# radio.net
KiCad netlist of a schematic drawn in EAGLE
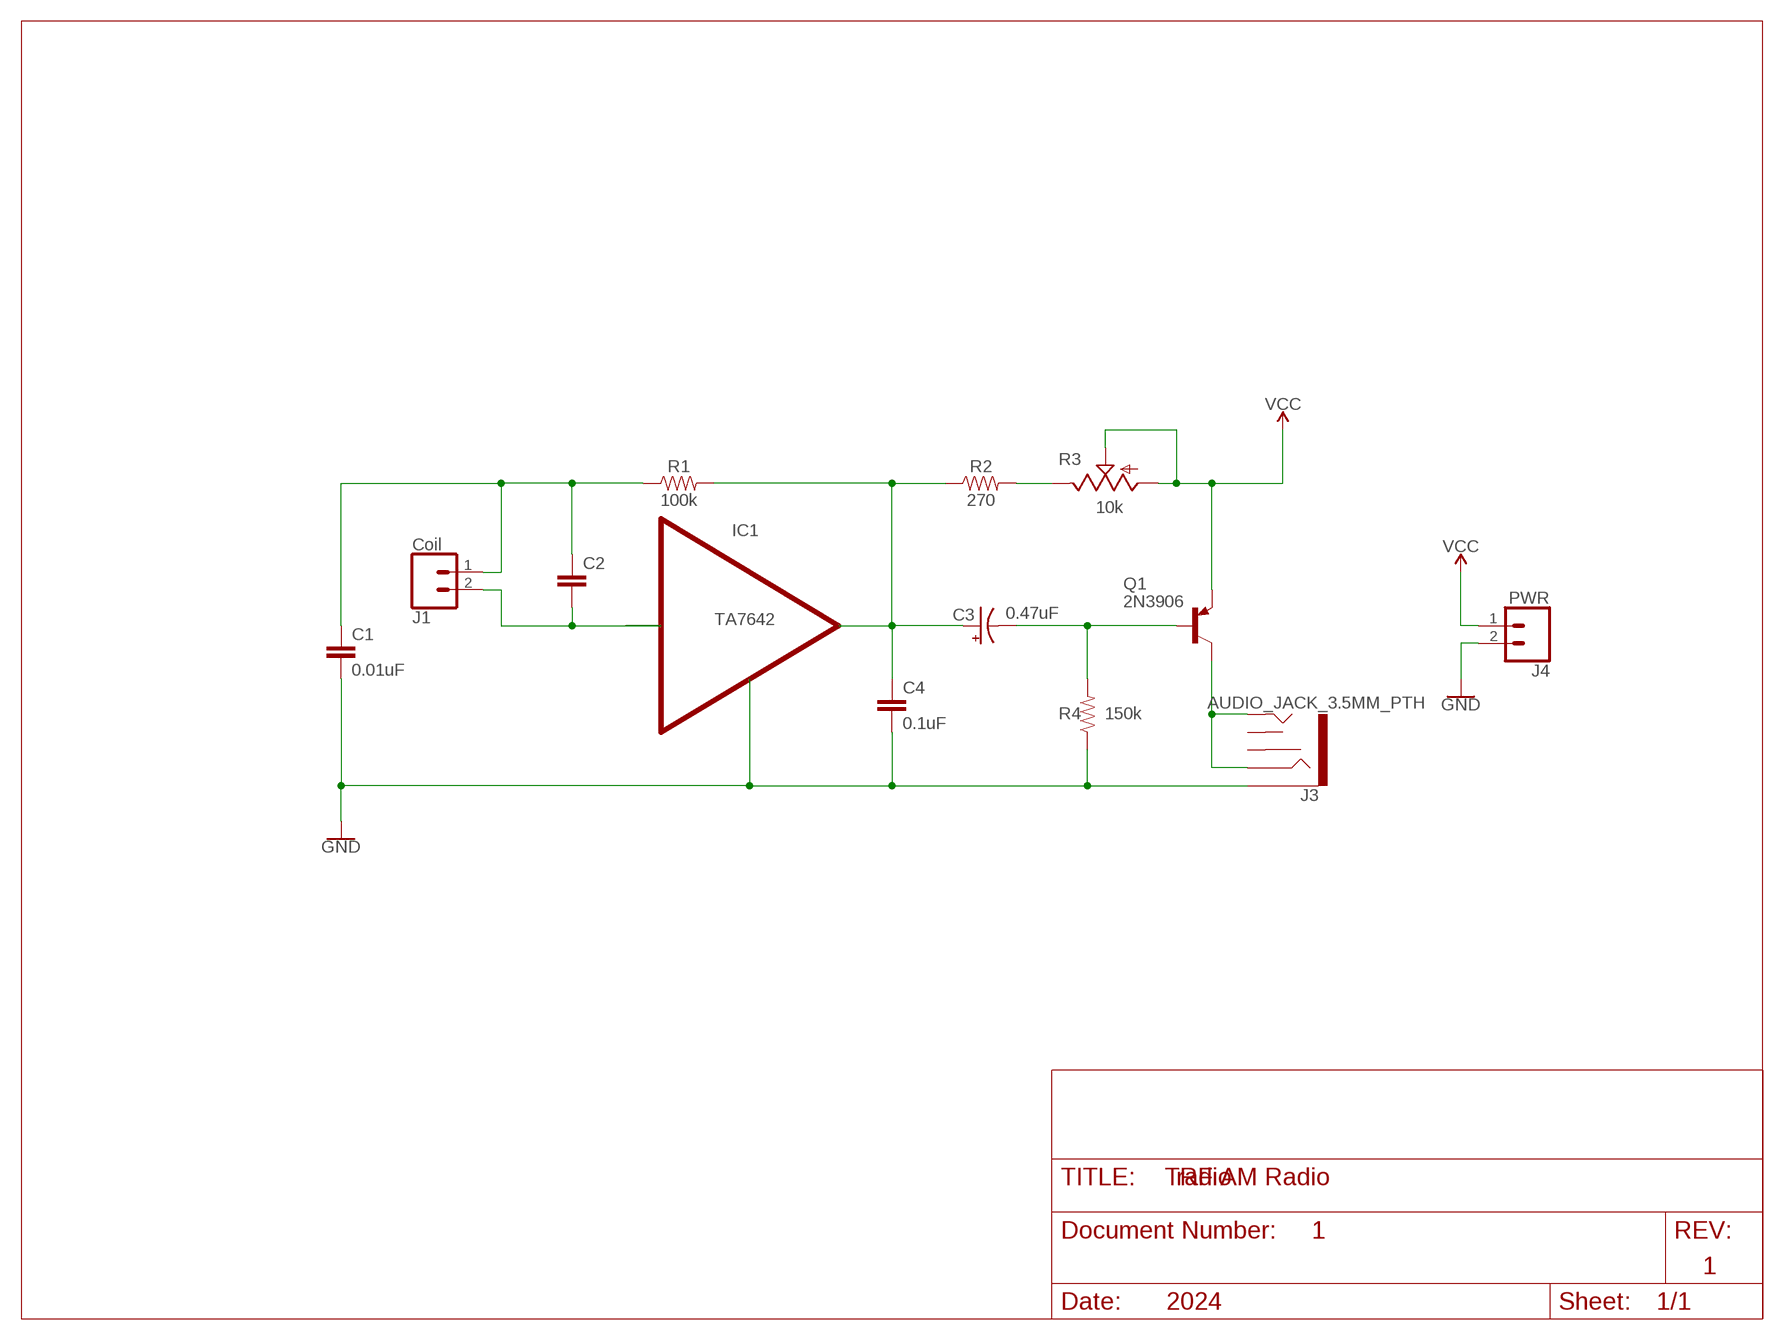
[diagram p0: schematic, sheet 1]

(export (version "E")
  (design (tool "Eeschema 10.0.6"))
  (components
    (comp (ref "C1")
      (value "0.01uF")
      (footprint "eagle-import:CAP-PTH-2.54")
      (libsource (lib "eagle-import") (part "22PF-PTH-2.54MM-200V-5%"))
    )
    (comp (ref "C2")
      (value "22PF-PTH-2.54MM-200V-5%")
      (footprint "eagle-import:CAP-PTH-2.54")
      (libsource (lib "eagle-import") (part "22PF-PTH-2.54MM-200V-5%"))
    )
    (comp (ref "C3")
      (value "0.47uF")
      (footprint "eagle-import:CPOL-RADIAL-2.5MM-5MM")
      (libsource (lib "eagle-import") (part "10UF-POLAR-RADIAL-2.5MM-25V-20%"))
    )
    (comp (ref "C4")
      (value "0.1uF")
      (footprint "eagle-import:CAP-PTH-2.54")
      (libsource (lib "eagle-import") (part "22PF-PTH-2.54MM-200V-5%"))
    )
    (comp (ref "IC1")
      (value "TA7642")
      (footprint "eagle-import:TO92")
      (libsource (lib "eagle-import") (part "TA7642"))
    )
    (comp (ref "J1")
      (value "Coil")
      (footprint "eagle-import:1X02")
      (libsource (lib "eagle-import") (part "CONN_02"))
    )
    (comp (ref "J3")
      (value "AUDIO_JACK_3.5MM_PTH")
      (footprint "eagle-import:AUDIO-JACK")
      (libsource (lib "eagle-import") (part "AUDIO_JACK_3.5MM_PTH"))
    )
    (comp (ref "J4")
      (value "PWR")
      (footprint "eagle-import:1X02")
      (libsource (lib "eagle-import") (part "CONN_02"))
    )
    (comp (ref "Q1")
      (value "2N3906")
      (footprint "eagle-import:TO92")
      (libsource (lib "eagle-import") (part "2N3906"))
    )
    (comp (ref "R1")
      (value "100k")
      (footprint "eagle-import:AXIAL-0.3")
      (libsource (lib "eagle-import") (part "RESISTORAXIAL-0.3"))
    )
    (comp (ref "R2")
      (value "270")
      (footprint "eagle-import:AXIAL-0.3")
      (libsource (lib "eagle-import") (part "RESISTORAXIAL-0.3"))
    )
    (comp (ref "R3")
      (value "10k")
      (footprint "eagle-import:B25P")
      (libsource (lib "eagle-import") (part "TRIM_US-B25P"))
    )
    (comp (ref "R4")
      (value "150k")
      (footprint "eagle-import:AXIAL-0.3")
      (libsource (lib "eagle-import") (part "RESISTORAXIAL-0.3"))
    )
  )
  (nets
    (net (code "1") (name "GND") (class "Default")
      (node (ref "C1") (pin "2") (pinfunction "2_2") (pintype "passive"))
      (node (ref "C4") (pin "2") (pinfunction "2_2") (pintype "passive"))
      (node (ref "IC1") (pin "2") (pinfunction "GND_2") (pintype "passive"))
      (node (ref "J3") (pin "SLEEVE") (pinfunction "SLEEVE_SLEEVE") (pintype "bidirectional"))
      (node (ref "J4") (pin "2") (pinfunction "2_2") (pintype "passive"))
      (node (ref "R4") (pin "P$1") (pinfunction "1_P$1") (pintype "passive"))
    )
    (net (code "2") (name "Net-(C3-+)") (class "Default")
      (node (ref "C3") (pin "1") (pinfunction "+_1") (pintype "passive"))
      (node (ref "C4") (pin "1") (pinfunction "1_1") (pintype "passive"))
      (node (ref "IC1") (pin "1") (pinfunction "OUT_1") (pintype "passive"))
      (node (ref "R1") (pin "P$2") (pinfunction "2_P$2") (pintype "passive"))
      (node (ref "R2") (pin "P$1") (pinfunction "1_P$1") (pintype "passive"))
    )
    (net (code "3") (name "Net-(C3--)") (class "Default")
      (node (ref "C3") (pin "2") (pinfunction "-_2") (pintype "passive"))
      (node (ref "Q1") (pin "2") (pinfunction "B_2") (pintype "passive"))
      (node (ref "R4") (pin "P$2") (pinfunction "2_P$2") (pintype "passive"))
    )
    (net (code "4") (name "Net-(IC1-INPUT)") (class "Default")
      (node (ref "C2") (pin "2") (pinfunction "2_2") (pintype "passive"))
      (node (ref "IC1") (pin "3") (pinfunction "INPUT_3") (pintype "passive"))
      (node (ref "J1") (pin "2") (pinfunction "2_2") (pintype "passive"))
    )
    (net (code "5") (name "Net-(Q1-C)") (class "Default")
      (node (ref "J3") (pin "RING") (pinfunction "RING_RING") (pintype "bidirectional"))
      (node (ref "J3") (pin "TIP") (pinfunction "TIP_TIP") (pintype "bidirectional"))
      (node (ref "Q1") (pin "1") (pinfunction "C_1") (pintype "passive"))
    )
    (net (code "6") (name "Net-(R1-1)") (class "Default")
      (node (ref "C1") (pin "1") (pinfunction "1_1") (pintype "passive"))
      (node (ref "C2") (pin "1") (pinfunction "1_1") (pintype "passive"))
      (node (ref "J1") (pin "1") (pinfunction "1_1") (pintype "passive"))
      (node (ref "R1") (pin "P$1") (pinfunction "1_P$1") (pintype "passive"))
    )
    (net (code "7") (name "Net-(R2-2)") (class "Default")
      (node (ref "R2") (pin "P$2") (pinfunction "2_P$2") (pintype "passive"))
      (node (ref "R3") (pin "E") (pinfunction "E_E") (pintype "passive"))
    )
    (net (code "8") (name "VCC") (class "Default")
      (node (ref "J4") (pin "1") (pinfunction "1_1") (pintype "passive"))
      (node (ref "Q1") (pin "3") (pinfunction "E_3") (pintype "passive"))
      (node (ref "R3") (pin "A") (pinfunction "A_A") (pintype "passive"))
      (node (ref "R3") (pin "S") (pinfunction "S_S") (pintype "passive"))
    )
    (net (code "9") (name "unconnected-(J3-PadRSH)") (class "Default")
      (node (ref "J3") (pin "RSH") (pinfunction "RSH_RSH") (pintype "bidirectional"))
    )
    (net (code "10") (name "unconnected-(J3-PadTSH)") (class "Default")
      (node (ref "J3") (pin "TSH") (pinfunction "TSH_TSH") (pintype "bidirectional"))
    )
  )
)
